# USB_Charger.net
KiCad netlist of a schematic drawn in Altium Designer
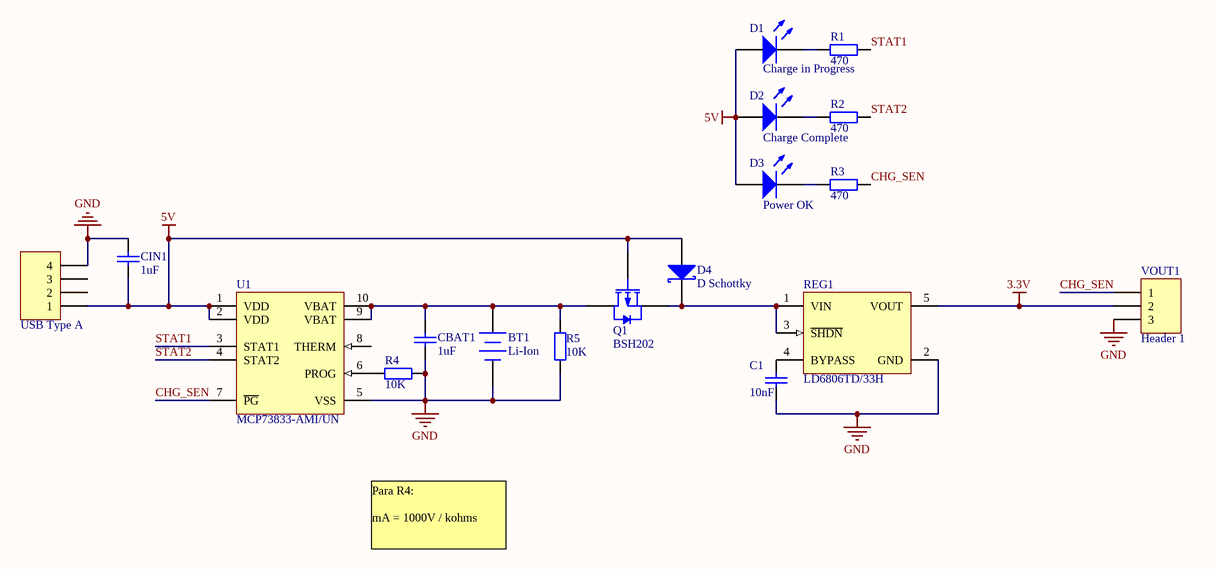
[diagram p0: USB_Charger.SchDoc]

(export (version "E")
  (design (tool "Eeschema 10.0.6"))
  (components
    (comp (ref "BT1")
      (value "Li-Ion")
      (footprint "BAT-2")
      (description "Multicell Battery")
      (fields (field (name "PUBLISHER") "Altium Limited"))
      (libsource (lib "Miscellaneous Devices") (part "Battery"))
    )
    (comp (ref "C1")
      (value "10nF")
      (footprint "1608[0603]")
      (description "Capacitor")
      (fields (field (name "Comment") "Cap") (field (name "PUBLISHER") "Altium Limited"))
      (libsource (lib "Miscellaneous Devices") (part "Cap"))
    )
    (comp (ref "CBAT1")
      (value "1uF")
      (footprint "1608[0603]")
      (description "Capacitor")
      (fields (field (name "Comment") "Cap") (field (name "PUBLISHER") "Altium Limited"))
      (libsource (lib "Miscellaneous Devices") (part "Cap"))
    )
    (comp (ref "CIN1")
      (value "1uF")
      (footprint "1608[0603]")
      (description "Capacitor")
      (fields (field (name "Comment") "Cap") (field (name "PUBLISHER") "Altium Limited"))
      (libsource (lib "Miscellaneous Devices") (part "Cap"))
    )
    (comp (ref "D1")
      (value "Charge in Progress")
      (footprint "2013[0805]")
      (libsource (lib "LibreriaComponentes") (part "LED SMD (0603)"))
    )
    (comp (ref "D2")
      (value "Charge Complete")
      (footprint "2013[0805]")
      (libsource (lib "LibreriaComponentes") (part "LED SMD (0603)"))
    )
    (comp (ref "D3")
      (value "Power OK")
      (footprint "2013[0805]")
      (libsource (lib "LibreriaComponentes") (part "LED SMD (0603)"))
    )
    (comp (ref "D4")
      (value "D Schottky")
      (footprint "SOD123/X.85")
      (description "Schottky Diode")
      (fields (field (name "PUBLISHER") "Altium Limited"))
      (libsource (lib "Miscellaneous Devices") (part "D Schottky"))
    )
    (comp (ref "P1")
      (value "USB Type A")
      (footprint "USBA_SMD")
      (description "Header, 4-Pin")
      (fields (field (name "PUBLISHER") "Altium Limited"))
      (libsource (lib "Miscellaneous Connectors") (part "Header 4"))
    )
    (comp (ref "Q1")
      (value "BSH202")
      (footprint "SOT23_M")
      (description "P-channel Enhancement Mode MOSFET")
      (fields (field (name "PUBLISHER") "Altium Limited"))
      (libsource (lib "Philips Discrete MOSFET - Low Power") (part "BSH202"))
    )
    (comp (ref "R1")
      (value "470")
      (footprint "1608[0603]")
      (description "Resistor")
      (fields (field (name "Comment") "Res2") (field (name "PUBLISHER") "Altium Limited"))
      (libsource (lib "") (part "Res2_1"))
    )
    (comp (ref "R2")
      (value "470")
      (footprint "1608[0603]")
      (description "Resistor")
      (fields (field (name "Comment") "Res2") (field (name "PUBLISHER") "Altium Limited"))
      (libsource (lib "") (part "Res2_1"))
    )
    (comp (ref "R3")
      (value "470")
      (footprint "1608[0603]")
      (description "Resistor")
      (fields (field (name "Comment") "Res2") (field (name "PUBLISHER") "Altium Limited"))
      (libsource (lib "") (part "Res2_1"))
    )
    (comp (ref "R4")
      (value "10K")
      (footprint "1608[0603]")
      (description "Resistor")
      (fields (field (name "Comment") "Res2") (field (name "PUBLISHER") "Altium Limited"))
      (libsource (lib "") (part "Res2_2"))
    )
    (comp (ref "R5")
      (value "10K")
      (footprint "1608[0603]")
      (description "Resistor")
      (fields (field (name "Comment") "Res2") (field (name "PUBLISHER") "Altium Limited"))
      (libsource (lib "Miscellaneous Devices") (part "Res2"))
    )
    (comp (ref "REG1")
      (value "LD6806TD/33H")
      (footprint "DBV005_N")
      (fields (field (name "PUBLISHER") "Altium Limited"))
      (libsource (lib "Microchip Power Mgt Line Regulator") (part "TC1014-1.8VCT713"))
    )
    (comp (ref "U1")
      (value "MCP73833-AMI/UN")
      (footprint "MSOP-UN10_N")
      (fields (field (name "PUBLISHER") "Altium Limited"))
      (libsource (lib "Microchip Power Mgt Battery Management") (part "MCP73833-AMI/UN"))
    )
    (comp (ref "VOUT1")
      (value "Header 1")
      (footprint "HDR1X3H")
      (description "Header, 3-Pin")
      (fields (field (name "PUBLISHER") "Altium Limited"))
      (libsource (lib "Miscellaneous Connectors") (part "Header 3"))
    )
  )
  (nets
    (net (code "1") (name "/CHG_SEN") (class "Default")
      (node (ref "R3") (pin "2") (pinfunction "2_2") (pintype "passive"))
      (node (ref "U1") (pin "7") (pinfunction "~{PG}_7") (pintype "open_collector"))
      (node (ref "VOUT1") (pin "1") (pinfunction "1_1") (pintype "passive"))
    )
    (net (code "2") (name "/STAT1") (class "Default")
      (node (ref "R1") (pin "2") (pinfunction "2_2") (pintype "passive"))
      (node (ref "U1") (pin "3") (pinfunction "STAT1_3") (pintype "open_collector"))
    )
    (net (code "3") (name "/STAT2") (class "Default")
      (node (ref "R2") (pin "2") (pinfunction "2_2") (pintype "passive"))
      (node (ref "U1") (pin "4") (pinfunction "STAT2_4") (pintype "open_collector"))
    )
    (net (code "4") (name "3.3V") (class "Default")
      (node (ref "REG1") (pin "5") (pinfunction "VOUT_5") (pintype "power_in"))
      (node (ref "VOUT1") (pin "2") (pinfunction "2_2") (pintype "passive"))
    )
    (net (code "5") (name "5V") (class "Default")
      (node (ref "CIN1") (pin "2") (pinfunction "2_2") (pintype "passive"))
      (node (ref "D1") (pin "1") (pinfunction "1_1") (pintype "passive"))
      (node (ref "D2") (pin "1") (pinfunction "1_1") (pintype "passive"))
      (node (ref "D3") (pin "1") (pinfunction "1_1") (pintype "passive"))
      (node (ref "D4") (pin "1") (pinfunction "A_1") (pintype "passive"))
      (node (ref "P1") (pin "1") (pinfunction "1_1") (pintype "passive"))
      (node (ref "Q1") (pin "1") (pinfunction "G_1") (pintype "passive"))
      (node (ref "U1") (pin "1") (pinfunction "VDD_1") (pintype "power_in"))
      (node (ref "U1") (pin "2") (pinfunction "VDD_2") (pintype "power_in"))
    )
    (net (code "6") (name "GND") (class "Default")
      (node (ref "BT1") (pin "2") (pinfunction "-_2") (pintype "passive"))
      (node (ref "C1") (pin "1") (pinfunction "1_1") (pintype "passive"))
      (node (ref "CBAT1") (pin "2") (pinfunction "2_2") (pintype "passive"))
      (node (ref "CIN1") (pin "1") (pinfunction "1_1") (pintype "passive"))
      (node (ref "P1") (pin "4") (pinfunction "4_4") (pintype "passive"))
      (node (ref "R4") (pin "1") (pinfunction "1_1") (pintype "passive"))
      (node (ref "R5") (pin "2") (pinfunction "2_2") (pintype "passive"))
      (node (ref "REG1") (pin "2") (pinfunction "GND_2") (pintype "power_in"))
      (node (ref "U1") (pin "5") (pinfunction "VSS_5") (pintype "power_in"))
      (node (ref "VOUT1") (pin "3") (pinfunction "3_3") (pintype "passive"))
    )
    (net (code "7") (name "Net-(BT1-+)") (class "Default")
      (node (ref "BT1") (pin "1") (pinfunction "+_1") (pintype "passive"))
      (node (ref "CBAT1") (pin "1") (pinfunction "1_1") (pintype "passive"))
      (node (ref "Q1") (pin "3") (pinfunction "D_3") (pintype "passive"))
      (node (ref "R5") (pin "1") (pinfunction "1_1") (pintype "passive"))
      (node (ref "U1") (pin "10") (pinfunction "VBAT_10") (pintype "power_in"))
      (node (ref "U1") (pin "9") (pinfunction "VBAT_9") (pintype "power_in"))
    )
    (net (code "8") (name "Net-(D1-Pad2)") (class "Default")
      (node (ref "D1") (pin "2") (pinfunction "2_2") (pintype "passive"))
      (node (ref "R1") (pin "1") (pinfunction "1_1") (pintype "passive"))
    )
    (net (code "9") (name "Net-(D2-Pad2)") (class "Default")
      (node (ref "D2") (pin "2") (pinfunction "2_2") (pintype "passive"))
      (node (ref "R2") (pin "1") (pinfunction "1_1") (pintype "passive"))
    )
    (net (code "10") (name "Net-(D3-Pad2)") (class "Default")
      (node (ref "D3") (pin "2") (pinfunction "2_2") (pintype "passive"))
      (node (ref "R3") (pin "1") (pinfunction "1_1") (pintype "passive"))
    )
    (net (code "11") (name "Net-(D4-K)") (class "Default")
      (node (ref "D4") (pin "2") (pinfunction "K_2") (pintype "passive"))
      (node (ref "Q1") (pin "2") (pinfunction "S_2") (pintype "passive"))
      (node (ref "REG1") (pin "1") (pinfunction "VIN_1") (pintype "power_in"))
      (node (ref "REG1") (pin "3") (pinfunction "~{SHDN}_3") (pintype "input"))
    )
    (net (code "12") (name "Net-(REG1-BYPASS)") (class "Default")
      (node (ref "C1") (pin "2") (pinfunction "2_2") (pintype "passive"))
      (node (ref "REG1") (pin "4") (pinfunction "BYPASS_4") (pintype "passive"))
    )
    (net (code "13") (name "Net-(U1-PROG)") (class "Default")
      (node (ref "R4") (pin "2") (pinfunction "2_2") (pintype "passive"))
      (node (ref "U1") (pin "6") (pinfunction "PROG_6") (pintype "input"))
    )
    (net (code "14") (name "unconnected-(P1-Pad2)") (class "Default")
      (node (ref "P1") (pin "2") (pinfunction "2_2") (pintype "passive"))
    )
    (net (code "15") (name "unconnected-(P1-Pad3)") (class "Default")
      (node (ref "P1") (pin "3") (pinfunction "3_3") (pintype "passive"))
    )
    (net (code "16") (name "unconnected-(U1-THERM-Pad8)") (class "Default")
      (node (ref "U1") (pin "8") (pinfunction "THERM_8") (pintype "input"))
    )
  )
)
